# DRV8844.net
KiCad netlist of a schematic drawn in Altium Designer
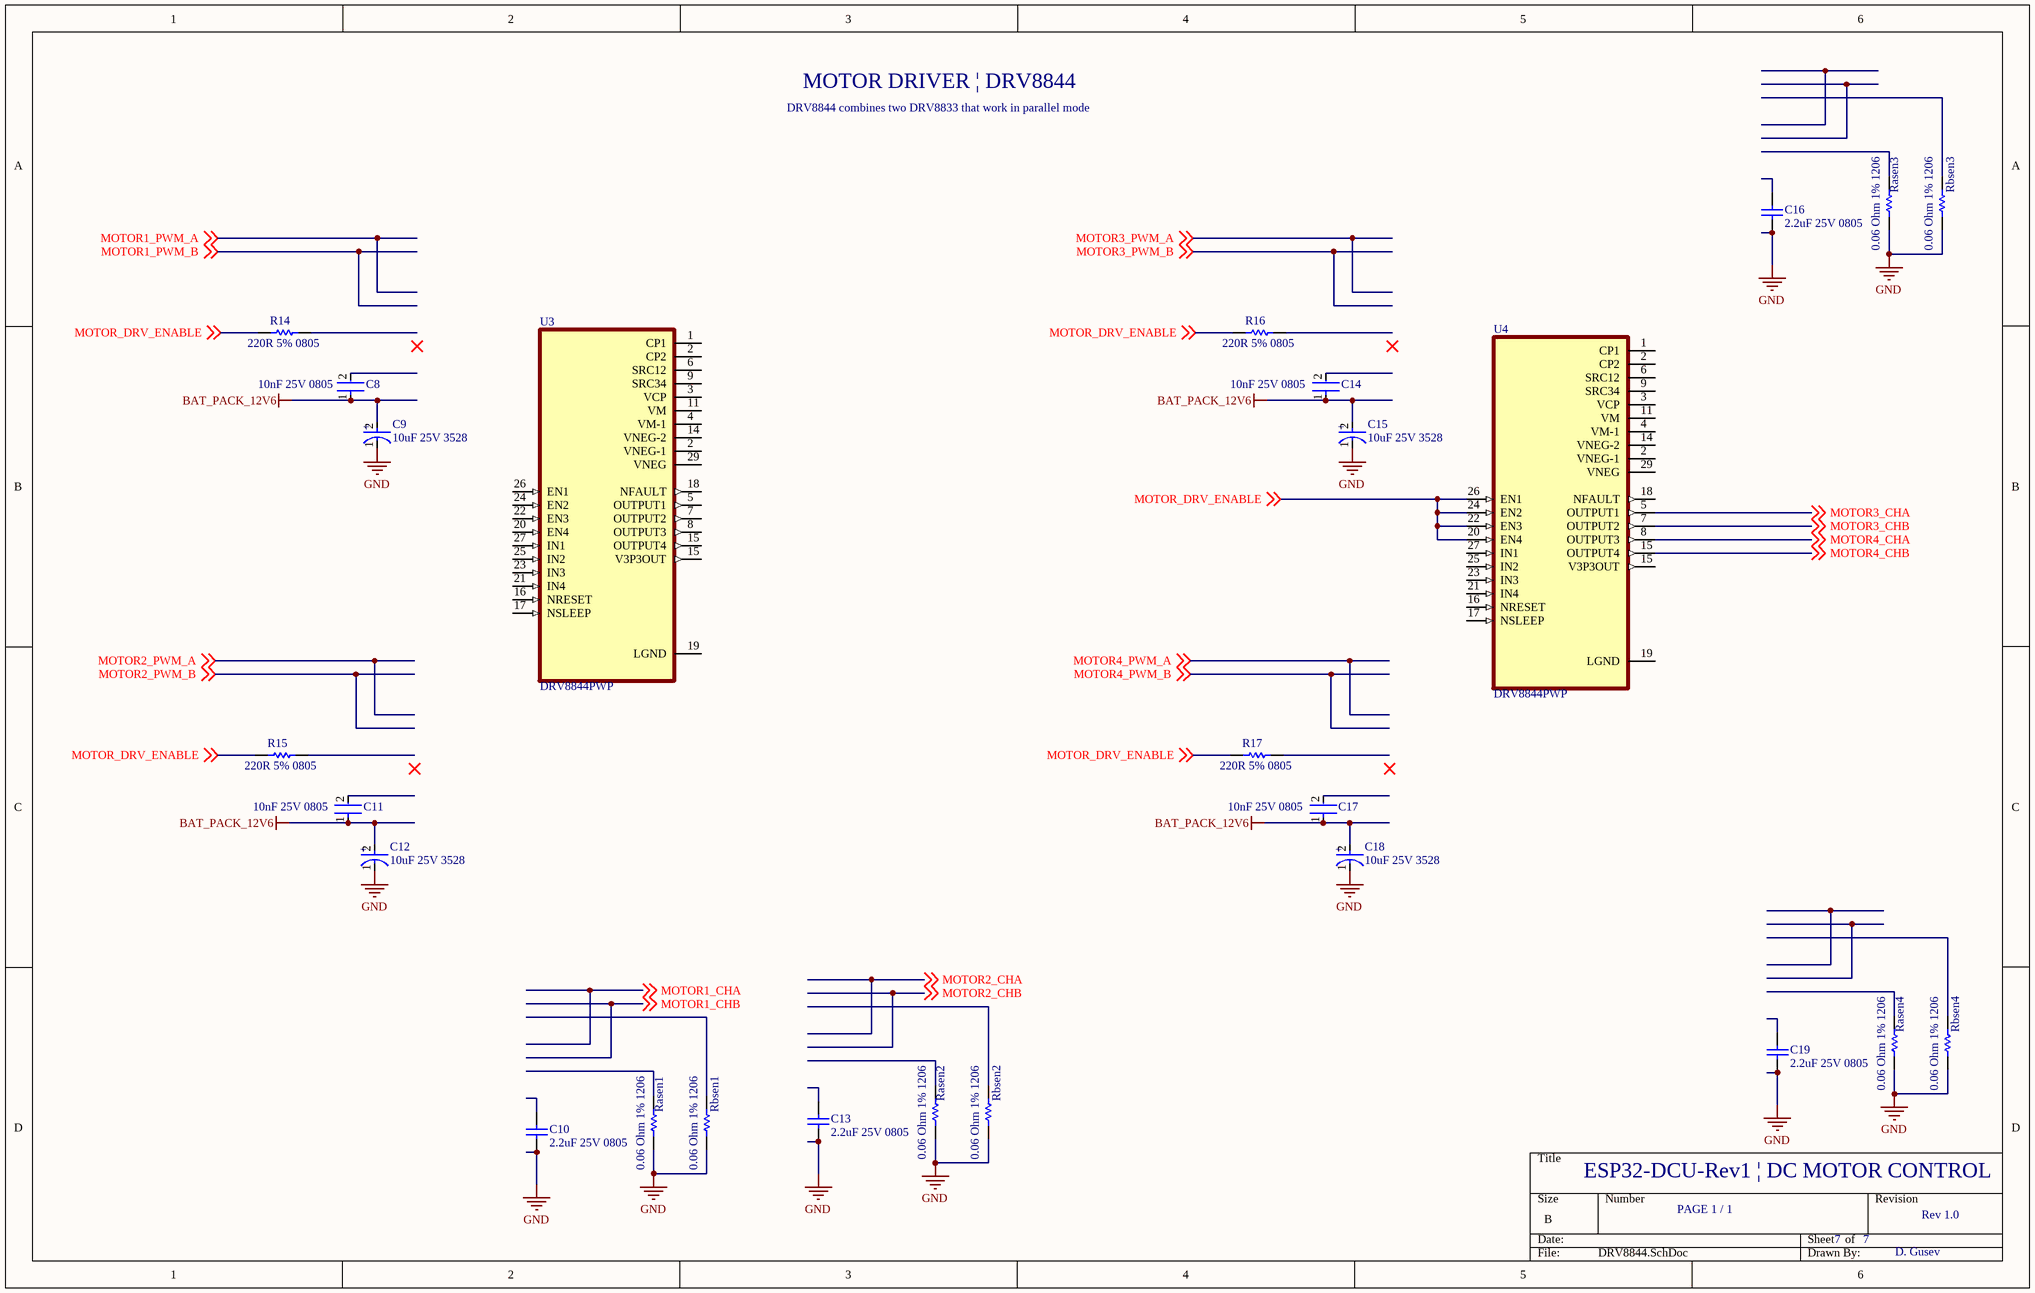
[diagram p0: DRV8844.SchDoc]

(export (version "E")
  (design (tool "Eeschema 10.0.6"))
  (components
    (comp (ref "C8")
      (value "10nF 25V 0805")
      (footprint "FP-C0805C-DN-MFG")
      (description "CAP CER 10000PF 25V 5% NP0 0805")
      (fields
        (field (name "OCTOPART") "https://octopart.com/c0805c103j3gactu-kemet-12563663")
        (field (name "TOLERANCE") "0.05")
      )
      (libsource (lib "Altium Content Vault") (part "b4654b650e69147ec39a6b967a45e02"))
    )
    (comp (ref "C9")
      (value "10uF 25V 3528")
      (footprint "FP-T491B106K025AT-MFG")
      (description "CAP TANT 10UF 10% 25V 1411")
      (fields (field (name "VOLTAGE") "25V") (field (name "TOLERANCE") "10%"))
      (libsource (lib "Altium Content Vault") (part "a00bbbee19879c290e62620ae7e47b1"))
    )
    (comp (ref "C10")
      (value "2.2uF 25V 0805")
      (footprint "CAPC2013X135X45ML10T25")
      (fields (field (name "PART NUMBER") "GRM21BF51E225ZA01L") (field (name "MANUFACTURER") "Murata"))
      (libsource (lib "Altium Content Vault") (part "CAP"))
    )
    (comp (ref "C11")
      (value "10nF 25V 0805")
      (footprint "FP-C0805C-DN-MFG")
      (description "CAP CER 10000PF 25V 5% NP0 0805")
      (fields
        (field (name "OCTOPART") "https://octopart.com/c0805c103j3gactu-kemet-12563663")
        (field (name "TOLERANCE") "0.05")
      )
      (libsource (lib "Altium Content Vault") (part "b4654b650e69147ec39a6b967a45e02"))
    )
    (comp (ref "C12")
      (value "10uF 25V 3528")
      (footprint "FP-T491B106K025AT-MFG")
      (description "CAP TANT 10UF 10% 25V 1411")
      (fields (field (name "VOLTAGE") "25V") (field (name "TOLERANCE") "10%"))
      (libsource (lib "Altium Content Vault") (part "a00bbbee19879c290e62620ae7e47b1"))
    )
    (comp (ref "C13")
      (value "2.2uF 25V 0805")
      (footprint "CAPC2013X135X45ML10T25")
      (fields (field (name "PART NUMBER") "GRM21BF51E225ZA01L") (field (name "MANUFACTURER") "Murata"))
      (libsource (lib "Altium Content Vault") (part "CAP"))
    )
    (comp (ref "C14")
      (value "10nF 25V 0805")
      (footprint "FP-C0805C-DN-MFG")
      (description "CAP CER 10000PF 25V 5% NP0 0805")
      (fields
        (field (name "OCTOPART") "https://octopart.com/c0805c103j3gactu-kemet-12563663")
        (field (name "TOLERANCE") "0.05")
      )
      (libsource (lib "Altium Content Vault") (part "b4654b650e69147ec39a6b967a45e02"))
    )
    (comp (ref "C15")
      (value "10uF 25V 3528")
      (footprint "FP-T491B106K025AT-MFG")
      (description "CAP TANT 10UF 10% 25V 1411")
      (fields (field (name "VOLTAGE") "25V") (field (name "TOLERANCE") "10%"))
      (libsource (lib "Altium Content Vault") (part "a00bbbee19879c290e62620ae7e47b1"))
    )
    (comp (ref "C16")
      (value "2.2uF 25V 0805")
      (footprint "CAPC2013X135X45ML10T25")
      (fields (field (name "PART NUMBER") "GRM21BF51E225ZA01L") (field (name "MANUFACTURER") "Murata"))
      (libsource (lib "Altium Content Vault") (part "CAP"))
    )
    (comp (ref "C17")
      (value "10nF 25V 0805")
      (footprint "FP-C0805C-DN-MFG")
      (description "CAP CER 10000PF 25V 5% NP0 0805")
      (fields
        (field (name "OCTOPART") "https://octopart.com/c0805c103j3gactu-kemet-12563663")
        (field (name "TOLERANCE") "0.05")
      )
      (libsource (lib "Altium Content Vault") (part "b4654b650e69147ec39a6b967a45e02"))
    )
    (comp (ref "C18")
      (value "10uF 25V 3528")
      (footprint "FP-T491B106K025AT-MFG")
      (description "CAP TANT 10UF 10% 25V 1411")
      (fields (field (name "VOLTAGE") "25V") (field (name "TOLERANCE") "10%"))
      (libsource (lib "Altium Content Vault") (part "a00bbbee19879c290e62620ae7e47b1"))
    )
    (comp (ref "C19")
      (value "2.2uF 25V 0805")
      (footprint "CAPC2013X135X45ML10T25")
      (fields (field (name "PART NUMBER") "GRM21BF51E225ZA01L") (field (name "MANUFACTURER") "Murata"))
      (libsource (lib "Altium Content Vault") (part "CAP"))
    )
    (comp (ref "R14")
      (value "220R 5% 0805")
      (footprint "RESC2013X60X40NL20T25")
      (fields (field (name "MANUFACTURER") "Panasonic") (field (name "PART NUMBER") "ERA6AEB221V"))
      (libsource (lib "Altium Content Vault") (part "RES"))
    )
    (comp (ref "R15")
      (value "220R 5% 0805")
      (footprint "RESC2013X60X40NL20T25")
      (fields (field (name "MANUFACTURER") "Panasonic") (field (name "PART NUMBER") "ERA6AEB221V"))
      (libsource (lib "Altium Content Vault") (part "RES"))
    )
    (comp (ref "R16")
      (value "220R 5% 0805")
      (footprint "RESC2013X60X40NL20T25")
      (fields (field (name "MANUFACTURER") "Panasonic") (field (name "PART NUMBER") "ERA6AEB221V"))
      (libsource (lib "Altium Content Vault") (part "RES"))
    )
    (comp (ref "R17")
      (value "220R 5% 0805")
      (footprint "RESC2013X60X40NL20T25")
      (fields (field (name "MANUFACTURER") "Panasonic") (field (name "PART NUMBER") "ERA6AEB221V"))
      (libsource (lib "Altium Content Vault") (part "RES"))
    )
    (comp (ref "Rasen1")
      (value "0.06 Ohm 1% 1206")
      (footprint "RESC3216X89X51NL25T25")
      (fields (field (name "MANUFACTURER") "Vishay Dale") (field (name "PART NUMBER") "WSL1206R0600FEA"))
      (libsource (lib "Altium Content Vault") (part "RES"))
    )
    (comp (ref "Rasen2")
      (value "0.06 Ohm 1% 1206")
      (footprint "RESC3216X89X51NL25T25")
      (fields (field (name "MANUFACTURER") "Vishay Dale") (field (name "PART NUMBER") "WSL1206R0600FEA"))
      (libsource (lib "Altium Content Vault") (part "RES"))
    )
    (comp (ref "Rasen3")
      (value "0.06 Ohm 1% 1206")
      (footprint "RESC3216X89X51NL25T25")
      (fields (field (name "MANUFACTURER") "Vishay Dale") (field (name "PART NUMBER") "WSL1206R0600FEA"))
      (libsource (lib "Altium Content Vault") (part "RES"))
    )
    (comp (ref "Rasen4")
      (value "0.06 Ohm 1% 1206")
      (footprint "RESC3216X89X51NL25T25")
      (fields (field (name "MANUFACTURER") "Vishay Dale") (field (name "PART NUMBER") "WSL1206R0600FEA"))
      (libsource (lib "Altium Content Vault") (part "RES"))
    )
    (comp (ref "Rbsen1")
      (value "0.06 Ohm 1% 1206")
      (footprint "RESC3216X89X51NL25T25")
      (fields (field (name "MANUFACTURER") "Vishay Dale") (field (name "PART NUMBER") "WSL1206R0600FEA"))
      (libsource (lib "Altium Content Vault") (part "RES"))
    )
    (comp (ref "Rbsen2")
      (value "0.06 Ohm 1% 1206")
      (footprint "RESC3216X89X51NL25T25")
      (fields (field (name "MANUFACTURER") "Vishay Dale") (field (name "PART NUMBER") "WSL1206R0600FEA"))
      (libsource (lib "Altium Content Vault") (part "RES"))
    )
    (comp (ref "Rbsen3")
      (value "0.06 Ohm 1% 1206")
      (footprint "RESC3216X89X51NL25T25")
      (fields (field (name "MANUFACTURER") "Vishay Dale") (field (name "PART NUMBER") "WSL1206R0600FEA"))
      (libsource (lib "Altium Content Vault") (part "RES"))
    )
    (comp (ref "Rbsen4")
      (value "0.06 Ohm 1% 1206")
      (footprint "RESC3216X89X51NL25T25")
      (fields (field (name "MANUFACTURER") "Vishay Dale") (field (name "PART NUMBER") "WSL1206R0600FEA"))
      (libsource (lib "Altium Content Vault") (part "RES"))
    )
    (comp (ref "U3")
      (value "DRV8844PWP")
      (footprint "DRV8844")
      (fields (field (name "MF") "Texas Instruments"))
      (libsource (lib "ddrlegobrick") (part "DRV8844PWP"))
    )
    (comp (ref "U4")
      (value "DRV8844PWP")
      (footprint "DRV8844")
      (fields (field (name "MF") "Texas Instruments"))
      (libsource (lib "ddrlegobrick") (part "DRV8844PWP"))
    )
  )
  (nets
    (net (code "1") (name "BAT_PACK_12V6") (class "Default")
      (node (ref "C11") (pin "1") (pinfunction "1_1") (pintype "passive"))
      (node (ref "C12") (pin "2") (pinfunction "A_2") (pintype "passive"))
      (node (ref "C14") (pin "1") (pinfunction "1_1") (pintype "passive"))
      (node (ref "C15") (pin "2") (pinfunction "A_2") (pintype "passive"))
      (node (ref "C17") (pin "1") (pinfunction "1_1") (pintype "passive"))
      (node (ref "C18") (pin "2") (pinfunction "A_2") (pintype "passive"))
      (node (ref "C8") (pin "1") (pinfunction "1_1") (pintype "passive"))
      (node (ref "C9") (pin "2") (pinfunction "A_2") (pintype "passive"))
    )
    (net (code "2") (name "GND") (class "Default")
      (node (ref "C10") (pin "1") (pinfunction "1_1") (pintype "passive"))
      (node (ref "C12") (pin "1") (pinfunction "C_1") (pintype "passive"))
      (node (ref "C13") (pin "1") (pinfunction "1_1") (pintype "passive"))
      (node (ref "C15") (pin "1") (pinfunction "C_1") (pintype "passive"))
      (node (ref "C16") (pin "1") (pinfunction "1_1") (pintype "passive"))
      (node (ref "C18") (pin "1") (pinfunction "C_1") (pintype "passive"))
      (node (ref "C19") (pin "1") (pinfunction "1_1") (pintype "passive"))
      (node (ref "C9") (pin "1") (pinfunction "C_1") (pintype "passive"))
      (node (ref "Rasen1") (pin "1") (pinfunction "1_1") (pintype "passive"))
      (node (ref "Rasen2") (pin "1") (pinfunction "1_1") (pintype "passive"))
      (node (ref "Rasen3") (pin "1") (pinfunction "1_1") (pintype "passive"))
      (node (ref "Rasen4") (pin "1") (pinfunction "1_1") (pintype "passive"))
      (node (ref "Rbsen1") (pin "1") (pinfunction "1_1") (pintype "passive"))
      (node (ref "Rbsen2") (pin "1") (pinfunction "1_1") (pintype "passive"))
      (node (ref "Rbsen3") (pin "1") (pinfunction "1_1") (pintype "passive"))
      (node (ref "Rbsen4") (pin "1") (pinfunction "1_1") (pintype "passive"))
    )
    (net (code "11") (name "MOTOR3_CHA") (class "Default")
      (node (ref "U4") (pin "5") (pinfunction "OUTPUT1_5") (pintype "output"))
    )
    (net (code "12") (name "MOTOR3_CHB") (class "Default")
      (node (ref "U4") (pin "7") (pinfunction "OUTPUT2_7") (pintype "output"))
    )
    (net (code "15") (name "MOTOR4_CHA") (class "Default")
      (node (ref "U4") (pin "8") (pinfunction "OUTPUT3_8") (pintype "output"))
    )
    (net (code "16") (name "MOTOR4_CHB") (class "Default")
      (node (ref "U4") (pin "15") (pinfunction "OUTPUT4_15") (pintype "output"))
    )
    (net (code "19") (name "MOTOR_DRV_ENABLE") (class "Default")
      (node (ref "R14") (pin "1") (pinfunction "1_1") (pintype "passive"))
      (node (ref "R15") (pin "1") (pinfunction "1_1") (pintype "passive"))
      (node (ref "R16") (pin "1") (pinfunction "1_1") (pintype "passive"))
      (node (ref "R17") (pin "1") (pinfunction "1_1") (pintype "passive"))
      (node (ref "U4") (pin "20") (pinfunction "EN4_20") (pintype "input"))
      (node (ref "U4") (pin "22") (pinfunction "EN3_22") (pintype "input"))
      (node (ref "U4") (pin "24") (pinfunction "EN2_24") (pintype "input"))
      (node (ref "U4") (pin "26") (pinfunction "EN1_26") (pintype "input"))
    )
    (net (code "20") (name "unconnected-(C8-Pad2)") (class "Default")
      (node (ref "C8") (pin "2") (pinfunction "2_2") (pintype "passive"))
    )
    (net (code "21") (name "unconnected-(C10-Pad2)") (class "Default")
      (node (ref "C10") (pin "2") (pinfunction "2_2") (pintype "passive"))
    )
    (net (code "22") (name "unconnected-(C11-Pad2)") (class "Default")
      (node (ref "C11") (pin "2") (pinfunction "2_2") (pintype "passive"))
    )
    (net (code "23") (name "unconnected-(C13-Pad2)") (class "Default")
      (node (ref "C13") (pin "2") (pinfunction "2_2") (pintype "passive"))
    )
    (net (code "24") (name "unconnected-(C14-Pad2)") (class "Default")
      (node (ref "C14") (pin "2") (pinfunction "2_2") (pintype "passive"))
    )
    (net (code "25") (name "unconnected-(C16-Pad2)") (class "Default")
      (node (ref "C16") (pin "2") (pinfunction "2_2") (pintype "passive"))
    )
    (net (code "26") (name "unconnected-(C17-Pad2)") (class "Default")
      (node (ref "C17") (pin "2") (pinfunction "2_2") (pintype "passive"))
    )
    (net (code "27") (name "unconnected-(C19-Pad2)") (class "Default")
      (node (ref "C19") (pin "2") (pinfunction "2_2") (pintype "passive"))
    )
    (net (code "28") (name "unconnected-(R14-Pad2)") (class "Default")
      (node (ref "R14") (pin "2") (pinfunction "2_2") (pintype "passive"))
    )
    (net (code "29") (name "unconnected-(R15-Pad2)") (class "Default")
      (node (ref "R15") (pin "2") (pinfunction "2_2") (pintype "passive"))
    )
    (net (code "30") (name "unconnected-(R16-Pad2)") (class "Default")
      (node (ref "R16") (pin "2") (pinfunction "2_2") (pintype "passive"))
    )
    (net (code "31") (name "unconnected-(R17-Pad2)") (class "Default")
      (node (ref "R17") (pin "2") (pinfunction "2_2") (pintype "passive"))
    )
    (net (code "32") (name "unconnected-(Rasen1-Pad2)") (class "Default")
      (node (ref "Rasen1") (pin "2") (pinfunction "2_2") (pintype "passive"))
    )
    (net (code "33") (name "unconnected-(Rasen2-Pad2)") (class "Default")
      (node (ref "Rasen2") (pin "2") (pinfunction "2_2") (pintype "passive"))
    )
    (net (code "34") (name "unconnected-(Rasen3-Pad2)") (class "Default")
      (node (ref "Rasen3") (pin "2") (pinfunction "2_2") (pintype "passive"))
    )
    (net (code "35") (name "unconnected-(Rasen4-Pad2)") (class "Default")
      (node (ref "Rasen4") (pin "2") (pinfunction "2_2") (pintype "passive"))
    )
    (net (code "36") (name "unconnected-(Rbsen1-Pad2)") (class "Default")
      (node (ref "Rbsen1") (pin "2") (pinfunction "2_2") (pintype "passive"))
    )
    (net (code "37") (name "unconnected-(Rbsen2-Pad2)") (class "Default")
      (node (ref "Rbsen2") (pin "2") (pinfunction "2_2") (pintype "passive"))
    )
    (net (code "38") (name "unconnected-(Rbsen3-Pad2)") (class "Default")
      (node (ref "Rbsen3") (pin "2") (pinfunction "2_2") (pintype "passive"))
    )
    (net (code "39") (name "unconnected-(Rbsen4-Pad2)") (class "Default")
      (node (ref "Rbsen4") (pin "2") (pinfunction "2_2") (pintype "passive"))
    )
    (net (code "40") (name "unconnected-(U3-CP1-Pad1)") (class "Default")
      (node (ref "U3") (pin "1") (pinfunction "CP1_1") (pintype "power_in"))
    )
    (net (code "41") (name "unconnected-(U3-CP2-Pad2)") (class "Default")
      (node (ref "U3") (pin "2") (pinfunction "CP2_2") (pintype "power_in"))
    )
    (net (code "42") (name "unconnected-(U3-EN1-Pad26)") (class "Default")
      (node (ref "U3") (pin "26") (pinfunction "EN1_26") (pintype "input"))
    )
    (net (code "43") (name "unconnected-(U3-EN2-Pad24)") (class "Default")
      (node (ref "U3") (pin "24") (pinfunction "EN2_24") (pintype "input"))
    )
    (net (code "44") (name "unconnected-(U3-EN3-Pad22)") (class "Default")
      (node (ref "U3") (pin "22") (pinfunction "EN3_22") (pintype "input"))
    )
    (net (code "45") (name "unconnected-(U3-EN4-Pad20)") (class "Default")
      (node (ref "U3") (pin "20") (pinfunction "EN4_20") (pintype "input"))
    )
    (net (code "46") (name "unconnected-(U3-IN1-Pad27)") (class "Default")
      (node (ref "U3") (pin "27") (pinfunction "IN1_27") (pintype "input"))
    )
    (net (code "47") (name "unconnected-(U3-IN2-Pad25)") (class "Default")
      (node (ref "U3") (pin "25") (pinfunction "IN2_25") (pintype "input"))
    )
    (net (code "48") (name "unconnected-(U3-IN3-Pad23)") (class "Default")
      (node (ref "U3") (pin "23") (pinfunction "IN3_23") (pintype "input"))
    )
    (net (code "49") (name "unconnected-(U3-IN4-Pad21)") (class "Default")
      (node (ref "U3") (pin "21") (pinfunction "IN4_21") (pintype "input"))
    )
    (net (code "50") (name "unconnected-(U3-LGND-Pad19)") (class "Default")
      (node (ref "U3") (pin "19") (pinfunction "LGND_19") (pintype "power_in"))
    )
    (net (code "51") (name "unconnected-(U3-NFAULT-Pad18)") (class "Default")
      (node (ref "U3") (pin "18") (pinfunction "NFAULT_18") (pintype "output"))
    )
    (net (code "52") (name "unconnected-(U3-NRESET-Pad16)") (class "Default")
      (node (ref "U3") (pin "16") (pinfunction "NRESET_16") (pintype "input"))
    )
    (net (code "53") (name "unconnected-(U3-NSLEEP-Pad17)") (class "Default")
      (node (ref "U3") (pin "17") (pinfunction "NSLEEP_17") (pintype "input"))
    )
    (net (code "54") (name "unconnected-(U3-OUTPUT1-Pad5)") (class "Default")
      (node (ref "U3") (pin "5") (pinfunction "OUTPUT1_5") (pintype "output"))
    )
    (net (code "55") (name "unconnected-(U3-OUTPUT2-Pad7)") (class "Default")
      (node (ref "U3") (pin "7") (pinfunction "OUTPUT2_7") (pintype "output"))
    )
    (net (code "56") (name "unconnected-(U3-OUTPUT3-Pad8)") (class "Default")
      (node (ref "U3") (pin "8") (pinfunction "OUTPUT3_8") (pintype "output"))
    )
    (net (code "57") (name "unconnected-(U3-OUTPUT4-Pad15)") (class "Default")
      (node (ref "U3") (pin "15") (pinfunction "OUTPUT4_15") (pintype "output"))
    )
    (net (code "58") (name "unconnected-(U3-SRC12-Pad6)") (class "Default")
      (node (ref "U3") (pin "6") (pinfunction "SRC12_6") (pintype "power_in"))
    )
    (net (code "59") (name "unconnected-(U3-SRC34-Pad9)") (class "Default")
      (node (ref "U3") (pin "9") (pinfunction "SRC34_9") (pintype "power_in"))
    )
    (net (code "60") (name "unconnected-(U3-V3P3OUT-Pad15)") (class "Default")
      (node (ref "U3") (pin "15") (pinfunction "V3P3OUT_15") (pintype "output"))
    )
    (net (code "61") (name "unconnected-(U3-VCP-Pad3)") (class "Default")
      (node (ref "U3") (pin "3") (pinfunction "VCP_3") (pintype "power_in"))
    )
    (net (code "62") (name "unconnected-(U3-VM-1-Pad4)") (class "Default")
      (node (ref "U3") (pin "4") (pinfunction "VM-1_4") (pintype "power_in"))
    )
    (net (code "63") (name "unconnected-(U3-VM-Pad11)") (class "Default")
      (node (ref "U3") (pin "11") (pinfunction "VM_11") (pintype "power_in"))
    )
    (net (code "64") (name "unconnected-(U3-VNEG-1-Pad2)") (class "Default")
      (node (ref "U3") (pin "2") (pinfunction "VNEG-1_2") (pintype "power_in"))
    )
    (net (code "65") (name "unconnected-(U3-VNEG-2-Pad14)") (class "Default")
      (node (ref "U3") (pin "14") (pinfunction "VNEG-2_14") (pintype "power_in"))
    )
    (net (code "66") (name "unconnected-(U3-VNEG-Pad29)") (class "Default")
      (node (ref "U3") (pin "29") (pinfunction "VNEG_29") (pintype "power_in"))
    )
    (net (code "67") (name "unconnected-(U4-CP1-Pad1)") (class "Default")
      (node (ref "U4") (pin "1") (pinfunction "CP1_1") (pintype "power_in"))
    )
    (net (code "68") (name "unconnected-(U4-CP2-Pad2)") (class "Default")
      (node (ref "U4") (pin "2") (pinfunction "CP2_2") (pintype "power_in"))
    )
    (net (code "69") (name "unconnected-(U4-IN1-Pad27)") (class "Default")
      (node (ref "U4") (pin "27") (pinfunction "IN1_27") (pintype "input"))
    )
    (net (code "70") (name "unconnected-(U4-IN2-Pad25)") (class "Default")
      (node (ref "U4") (pin "25") (pinfunction "IN2_25") (pintype "input"))
    )
    (net (code "71") (name "unconnected-(U4-IN3-Pad23)") (class "Default")
      (node (ref "U4") (pin "23") (pinfunction "IN3_23") (pintype "input"))
    )
    (net (code "72") (name "unconnected-(U4-IN4-Pad21)") (class "Default")
      (node (ref "U4") (pin "21") (pinfunction "IN4_21") (pintype "input"))
    )
    (net (code "73") (name "unconnected-(U4-LGND-Pad19)") (class "Default")
      (node (ref "U4") (pin "19") (pinfunction "LGND_19") (pintype "power_in"))
    )
    (net (code "74") (name "unconnected-(U4-NFAULT-Pad18)") (class "Default")
      (node (ref "U4") (pin "18") (pinfunction "NFAULT_18") (pintype "output"))
    )
    (net (code "75") (name "unconnected-(U4-NRESET-Pad16)") (class "Default")
      (node (ref "U4") (pin "16") (pinfunction "NRESET_16") (pintype "input"))
    )
    (net (code "76") (name "unconnected-(U4-NSLEEP-Pad17)") (class "Default")
      (node (ref "U4") (pin "17") (pinfunction "NSLEEP_17") (pintype "input"))
    )
    (net (code "77") (name "unconnected-(U4-SRC12-Pad6)") (class "Default")
      (node (ref "U4") (pin "6") (pinfunction "SRC12_6") (pintype "power_in"))
    )
    (net (code "78") (name "unconnected-(U4-SRC34-Pad9)") (class "Default")
      (node (ref "U4") (pin "9") (pinfunction "SRC34_9") (pintype "power_in"))
    )
    (net (code "79") (name "unconnected-(U4-V3P3OUT-Pad15)") (class "Default")
      (node (ref "U4") (pin "15") (pinfunction "V3P3OUT_15") (pintype "output"))
    )
    (net (code "80") (name "unconnected-(U4-VCP-Pad3)") (class "Default")
      (node (ref "U4") (pin "3") (pinfunction "VCP_3") (pintype "power_in"))
    )
    (net (code "81") (name "unconnected-(U4-VM-1-Pad4)") (class "Default")
      (node (ref "U4") (pin "4") (pinfunction "VM-1_4") (pintype "power_in"))
    )
    (net (code "82") (name "unconnected-(U4-VM-Pad11)") (class "Default")
      (node (ref "U4") (pin "11") (pinfunction "VM_11") (pintype "power_in"))
    )
    (net (code "83") (name "unconnected-(U4-VNEG-1-Pad2)") (class "Default")
      (node (ref "U4") (pin "2") (pinfunction "VNEG-1_2") (pintype "power_in"))
    )
    (net (code "84") (name "unconnected-(U4-VNEG-2-Pad14)") (class "Default")
      (node (ref "U4") (pin "14") (pinfunction "VNEG-2_14") (pintype "power_in"))
    )
    (net (code "85") (name "unconnected-(U4-VNEG-Pad29)") (class "Default")
      (node (ref "U4") (pin "29") (pinfunction "VNEG_29") (pintype "power_in"))
    )
  )
)
